# cirrus-audio.net
KiCad netlist of a schematic drawn in Altium Designer
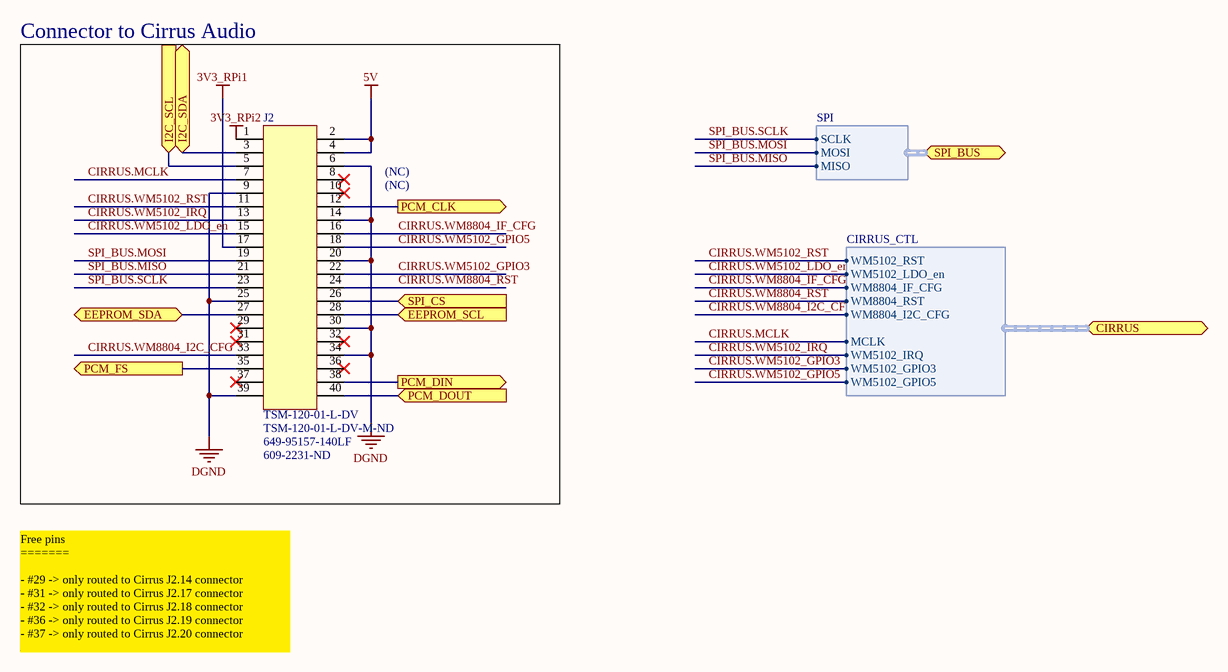
[diagram p0: cirrus-audio.SchDoc]

(export (version "E")
  (design (tool "Eeschema 10.0.6"))
  (components
    (comp (ref "J2")
      (value "TSM-120-01-L-DV")
      (footprint "TSM-120-04-L-DV")
      (description "Mating (male) connector for the RPi 3")
      (fields
        (field (name "SUPPLIER PART NUMBER 1") "TSM-120-01-L-DV-M-ND")
        (field (name "SUPPLIER PART NUMBER 2") "649-95157-140LF")
        (field (name "SUPPLIER PART NUMBER 3") "609-2231-ND")
      )
      (libsource (lib "MBoard") (part "TSM-120-01-L-DV"))
    )
  )
  (nets
    (net (code "3") (name "/CIRRUS.MCLK") (class "Default")
      (node (ref "J2") (pin "7") (pinfunction "7_7") (pintype "passive"))
    )
    (net (code "4") (name "/CIRRUS.WM5102_GPIO3") (class "Default")
      (node (ref "J2") (pin "22") (pinfunction "22_22") (pintype "passive"))
    )
    (net (code "5") (name "/CIRRUS.WM5102_GPIO5") (class "Default")
      (node (ref "J2") (pin "18") (pinfunction "18_18") (pintype "passive"))
    )
    (net (code "6") (name "/CIRRUS.WM5102_IRQ") (class "Default")
      (node (ref "J2") (pin "13") (pinfunction "13_13") (pintype "passive"))
    )
    (net (code "7") (name "/CIRRUS.WM5102_LDO_en") (class "Default")
      (node (ref "J2") (pin "15") (pinfunction "15_15") (pintype "passive"))
    )
    (net (code "8") (name "/CIRRUS.WM5102_RST") (class "Default")
      (node (ref "J2") (pin "11") (pinfunction "11_11") (pintype "passive"))
    )
    (net (code "9") (name "/CIRRUS.WM8804_I2C_CFG") (class "Default")
      (node (ref "J2") (pin "33") (pinfunction "33_33") (pintype "passive"))
    )
    (net (code "10") (name "/CIRRUS.WM8804_IF_CFG") (class "Default")
      (node (ref "J2") (pin "16") (pinfunction "16_16") (pintype "passive"))
    )
    (net (code "11") (name "/CIRRUS.WM8804_RST") (class "Default")
      (node (ref "J2") (pin "24") (pinfunction "24_24") (pintype "passive"))
    )
    (net (code "12") (name "/EEPROM_SCL") (class "Default")
      (node (ref "J2") (pin "28") (pinfunction "28_28") (pintype "passive"))
    )
    (net (code "13") (name "/EEPROM_SDA") (class "Default")
      (node (ref "J2") (pin "27") (pinfunction "27_27") (pintype "passive"))
    )
    (net (code "14") (name "/I2C_SCL") (class "Default")
      (node (ref "J2") (pin "5") (pinfunction "5_5") (pintype "passive"))
    )
    (net (code "15") (name "/I2C_SDA") (class "Default")
      (node (ref "J2") (pin "3") (pinfunction "3_3") (pintype "passive"))
    )
    (net (code "16") (name "/PCM_CLK") (class "Default")
      (node (ref "J2") (pin "12") (pinfunction "12_12") (pintype "passive"))
    )
    (net (code "17") (name "/PCM_DIN") (class "Default")
      (node (ref "J2") (pin "38") (pinfunction "38_38") (pintype "passive"))
    )
    (net (code "18") (name "/PCM_DOUT") (class "Default")
      (node (ref "J2") (pin "40") (pinfunction "40_40") (pintype "passive"))
    )
    (net (code "19") (name "/PCM_FS") (class "Default")
      (node (ref "J2") (pin "35") (pinfunction "35_35") (pintype "passive"))
    )
    (net (code "20") (name "/SPI_BUS.MISO") (class "Default")
      (node (ref "J2") (pin "21") (pinfunction "21_21") (pintype "passive"))
    )
    (net (code "21") (name "/SPI_BUS.MOSI") (class "Default")
      (node (ref "J2") (pin "19") (pinfunction "19_19") (pintype "passive"))
    )
    (net (code "22") (name "/SPI_BUS.SCLK") (class "Default")
      (node (ref "J2") (pin "23") (pinfunction "23_23") (pintype "passive"))
    )
    (net (code "23") (name "/SPI_CS") (class "Default")
      (node (ref "J2") (pin "26") (pinfunction "26_26") (pintype "passive"))
    )
    (net (code "26") (name "3V3_RPi1") (class "Default")
      (node (ref "J2") (pin "17") (pinfunction "17_17") (pintype "passive"))
    )
    (net (code "27") (name "3V3_RPi2") (class "Default")
      (node (ref "J2") (pin "1") (pinfunction "1_1") (pintype "passive"))
    )
    (net (code "28") (name "5V") (class "Default")
      (node (ref "J2") (pin "2") (pinfunction "2_2") (pintype "passive"))
      (node (ref "J2") (pin "4") (pinfunction "4_4") (pintype "passive"))
    )
    (net (code "29") (name "DGND") (class "Default")
      (node (ref "J2") (pin "14") (pinfunction "14_14") (pintype "passive"))
      (node (ref "J2") (pin "20") (pinfunction "20_20") (pintype "passive"))
      (node (ref "J2") (pin "25") (pinfunction "25_25") (pintype "passive"))
      (node (ref "J2") (pin "30") (pinfunction "30_30") (pintype "passive"))
      (node (ref "J2") (pin "34") (pinfunction "34_34") (pintype "passive"))
      (node (ref "J2") (pin "39") (pinfunction "39_39") (pintype "passive"))
      (node (ref "J2") (pin "6") (pinfunction "6_6") (pintype "passive"))
      (node (ref "J2") (pin "9") (pinfunction "9_9") (pintype "passive"))
    )
    (net (code "30") (name "unconnected-(J2-Pad8)") (class "Default")
      (node (ref "J2") (pin "8") (pinfunction "8_8") (pintype "passive+no_connect"))
    )
    (net (code "31") (name "unconnected-(J2-Pad10)") (class "Default")
      (node (ref "J2") (pin "10") (pinfunction "10_10") (pintype "passive+no_connect"))
    )
    (net (code "32") (name "unconnected-(J2-Pad29)") (class "Default")
      (node (ref "J2") (pin "29") (pinfunction "29_29") (pintype "passive+no_connect"))
    )
    (net (code "33") (name "unconnected-(J2-Pad31)") (class "Default")
      (node (ref "J2") (pin "31") (pinfunction "31_31") (pintype "passive+no_connect"))
    )
    (net (code "34") (name "unconnected-(J2-Pad32)") (class "Default")
      (node (ref "J2") (pin "32") (pinfunction "32_32") (pintype "passive+no_connect"))
    )
    (net (code "35") (name "unconnected-(J2-Pad36)") (class "Default")
      (node (ref "J2") (pin "36") (pinfunction "36_36") (pintype "passive+no_connect"))
    )
    (net (code "36") (name "unconnected-(J2-Pad37)") (class "Default")
      (node (ref "J2") (pin "37") (pinfunction "37_37") (pintype "passive+no_connect"))
    )
  )
)
